# MCP_Teensy.net
KiCad netlist of a schematic drawn in EAGLE
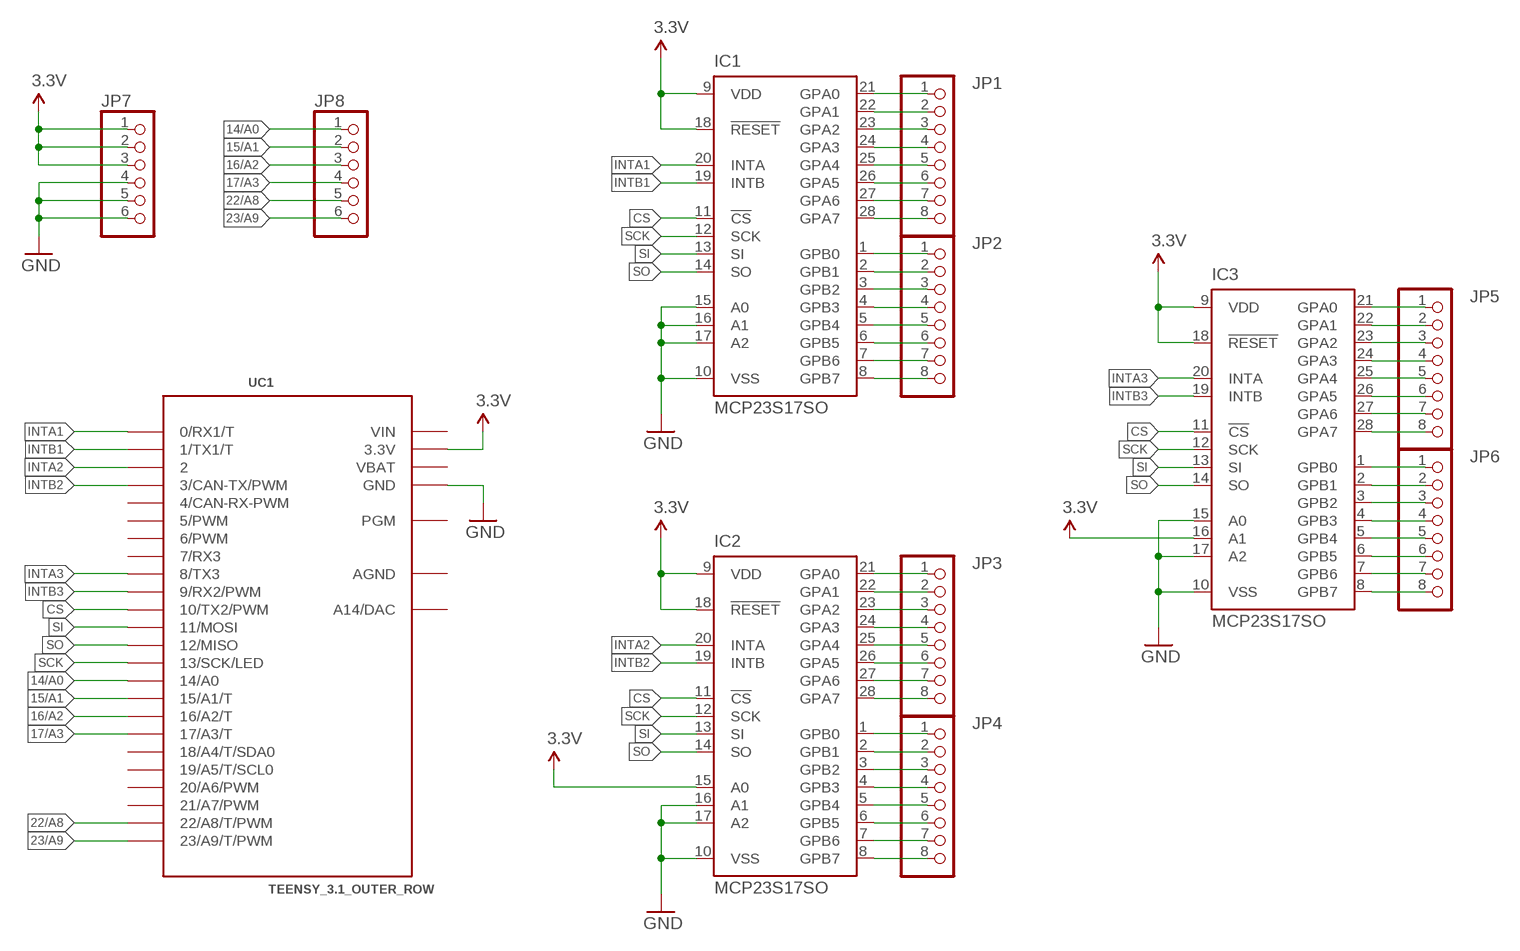
[diagram p0: schematic, sheet 1]

(export (version "E")
  (design (tool "Eeschema 10.0.6"))
  (components
    (comp (ref "IC1")
      (value "MCP23S17SO")
      (footprint "eagle-import:SO28W")
      (fields (field (name "MF") "MICROCHIP") (field (name "MPN") "MCP23S17-E/SO"))
      (libsource (lib "eagle-import") (part "MCP23S17SO"))
    )
    (comp (ref "IC2")
      (value "MCP23S17SO")
      (footprint "eagle-import:SO28W")
      (fields (field (name "MF") "MICROCHIP") (field (name "MPN") "MCP23S17-E/SO"))
      (libsource (lib "eagle-import") (part "MCP23S17SO"))
    )
    (comp (ref "IC3")
      (value "MCP23S17SO")
      (footprint "eagle-import:SO28W")
      (fields (field (name "MF") "MICROCHIP") (field (name "MPN") "MCP23S17-E/SO"))
      (libsource (lib "eagle-import") (part "MCP23S17SO"))
    )
    (comp (ref "JP1")
      (value "PINHD-1X8LOCK")
      (footprint "eagle-import:1X08-LOCK")
      (libsource (lib "eagle-import") (part "PINHD-1X8LOCK"))
    )
    (comp (ref "JP2")
      (value "PINHD-1X8LOCK")
      (footprint "eagle-import:1X08-LOCK")
      (libsource (lib "eagle-import") (part "PINHD-1X8LOCK"))
    )
    (comp (ref "JP3")
      (value "PINHD-1X8LOCK")
      (footprint "eagle-import:1X08-LOCK")
      (libsource (lib "eagle-import") (part "PINHD-1X8LOCK"))
    )
    (comp (ref "JP4")
      (value "PINHD-1X8LOCK")
      (footprint "eagle-import:1X08-LOCK")
      (libsource (lib "eagle-import") (part "PINHD-1X8LOCK"))
    )
    (comp (ref "JP5")
      (value "PINHD-1X8LOCK")
      (footprint "eagle-import:1X08-LOCK")
      (libsource (lib "eagle-import") (part "PINHD-1X8LOCK"))
    )
    (comp (ref "JP6")
      (value "PINHD-1X8LOCK")
      (footprint "eagle-import:1X08-LOCK")
      (libsource (lib "eagle-import") (part "PINHD-1X8LOCK"))
    )
    (comp (ref "JP7")
      (value "PINHD-1X6LOCK")
      (footprint "eagle-import:1X06-BIGLOCK")
      (libsource (lib "eagle-import") (part "PINHD-1X6LOCK"))
    )
    (comp (ref "JP8")
      (value "PINHD-1X6LOCK")
      (footprint "eagle-import:1X06-BIGLOCK")
      (libsource (lib "eagle-import") (part "PINHD-1X6LOCK"))
    )
    (comp (ref "UC1")
      (value "TEENSY_3.1_OUTER_ROW")
      (footprint "eagle-import:TEENSY3-OUTER_ROW")
      (libsource (lib "eagle-import") (part "TEENSY_3.1_OUTER_ROW"))
    )
  )
  (nets
    (net (code "1") (name "/AGND") (class "Default")
      (node (ref "UC1") (pin "AGND") (pinfunction "AGND_AGND") (pintype "power_in"))
    )
    (net (code "2") (name "/VBAT") (class "Default")
      (node (ref "UC1") (pin "VBAT") (pinfunction "VBAT_VBAT") (pintype "power_in"))
    )
    (net (code "3") (name "/VIN") (class "Default")
      (node (ref "UC1") (pin "VIN") (pinfunction "VIN_VIN") (pintype "power_in"))
    )
    (net (code "4") (name "3.3V") (class "Default")
      (node (ref "IC1") (pin "18") (pinfunction "~{RESET}_18") (pintype "input"))
      (node (ref "IC1") (pin "9") (pinfunction "VDD_9") (pintype "power_in"))
      (node (ref "IC2") (pin "15") (pinfunction "A0_15") (pintype "input"))
      (node (ref "IC2") (pin "18") (pinfunction "~{RESET}_18") (pintype "input"))
      (node (ref "IC2") (pin "9") (pinfunction "VDD_9") (pintype "power_in"))
      (node (ref "IC3") (pin "16") (pinfunction "A1_16") (pintype "input"))
      (node (ref "IC3") (pin "18") (pinfunction "~{RESET}_18") (pintype "input"))
      (node (ref "IC3") (pin "9") (pinfunction "VDD_9") (pintype "power_in"))
      (node (ref "JP7") (pin "1") (pinfunction "1_1") (pintype "passive"))
      (node (ref "JP7") (pin "2") (pinfunction "2_2") (pintype "passive"))
      (node (ref "JP7") (pin "3") (pinfunction "3_3") (pintype "passive"))
      (node (ref "UC1") (pin "3.3V") (pinfunction "3.3V_3.3V") (pintype "power_in"))
      (node (ref "UC1") (pin "3.3V1") (pinfunction "3.3V_3.3V1") (pintype "power_in"))
    )
    (net (code "5") (name "14{slash}A0") (class "Default")
      (node (ref "JP8") (pin "1") (pinfunction "1_1") (pintype "passive"))
      (node (ref "UC1") (pin "14/A0") (pinfunction "14/A0_14/A0") (pintype "bidirectional"))
    )
    (net (code "6") (name "15{slash}A1") (class "Default")
      (node (ref "JP8") (pin "2") (pinfunction "2_2") (pintype "passive"))
      (node (ref "UC1") (pin "15/A1") (pinfunction "15/A1/T_15/A1") (pintype "bidirectional"))
    )
    (net (code "7") (name "16{slash}A2") (class "Default")
      (node (ref "JP8") (pin "3") (pinfunction "3_3") (pintype "passive"))
      (node (ref "UC1") (pin "16/A2") (pinfunction "16/A2/T_16/A2") (pintype "bidirectional"))
    )
    (net (code "8") (name "17{slash}A3") (class "Default")
      (node (ref "JP8") (pin "4") (pinfunction "4_4") (pintype "passive"))
      (node (ref "UC1") (pin "17/A3") (pinfunction "17/A3/T_17/A3") (pintype "bidirectional"))
    )
    (net (code "9") (name "22{slash}A8") (class "Default")
      (node (ref "JP8") (pin "5") (pinfunction "5_5") (pintype "passive"))
      (node (ref "UC1") (pin "22/A8") (pinfunction "22/A8/T/PWM_22/A8") (pintype "bidirectional"))
    )
    (net (code "10") (name "23{slash}A9") (class "Default")
      (node (ref "JP8") (pin "6") (pinfunction "6_6") (pintype "passive"))
      (node (ref "UC1") (pin "23/A9") (pinfunction "23/A9/T/PWM_23/A9") (pintype "bidirectional"))
    )
    (net (code "11") (name "CS") (class "Default")
      (node (ref "IC1") (pin "11") (pinfunction "~{CS}_11") (pintype "input"))
      (node (ref "IC2") (pin "11") (pinfunction "~{CS}_11") (pintype "input"))
      (node (ref "IC3") (pin "11") (pinfunction "~{CS}_11") (pintype "input"))
      (node (ref "UC1") (pin "10") (pinfunction "10/TX2/PWM_10") (pintype "bidirectional"))
    )
    (net (code "12") (name "GND") (class "Default")
      (node (ref "IC1") (pin "10") (pinfunction "VSS_10") (pintype "power_in"))
      (node (ref "IC1") (pin "15") (pinfunction "A0_15") (pintype "input"))
      (node (ref "IC1") (pin "16") (pinfunction "A1_16") (pintype "input"))
      (node (ref "IC1") (pin "17") (pinfunction "A2_17") (pintype "input"))
      (node (ref "IC2") (pin "10") (pinfunction "VSS_10") (pintype "power_in"))
      (node (ref "IC2") (pin "16") (pinfunction "A1_16") (pintype "input"))
      (node (ref "IC2") (pin "17") (pinfunction "A2_17") (pintype "input"))
      (node (ref "IC3") (pin "10") (pinfunction "VSS_10") (pintype "power_in"))
      (node (ref "IC3") (pin "15") (pinfunction "A0_15") (pintype "input"))
      (node (ref "IC3") (pin "17") (pinfunction "A2_17") (pintype "input"))
      (node (ref "JP7") (pin "4") (pinfunction "4_4") (pintype "passive"))
      (node (ref "JP7") (pin "5") (pinfunction "5_5") (pintype "passive"))
      (node (ref "JP7") (pin "6") (pinfunction "6_6") (pintype "passive"))
      (node (ref "UC1") (pin "GND") (pinfunction "GND_GND") (pintype "power_in"))
      (node (ref "UC1") (pin "GND1") (pinfunction "GND_GND1") (pintype "power_in"))
    )
    (net (code "13") (name "INTA1") (class "Default")
      (node (ref "IC1") (pin "20") (pinfunction "INTA_20") (pintype "output"))
      (node (ref "UC1") (pin "0") (pinfunction "0/RX1/T_0") (pintype "bidirectional"))
    )
    (net (code "14") (name "INTA2") (class "Default")
      (node (ref "IC2") (pin "20") (pinfunction "INTA_20") (pintype "output"))
      (node (ref "UC1") (pin "2") (pinfunction "2_2") (pintype "bidirectional"))
    )
    (net (code "15") (name "INTA3") (class "Default")
      (node (ref "IC3") (pin "20") (pinfunction "INTA_20") (pintype "output"))
      (node (ref "UC1") (pin "8") (pinfunction "8/TX3_8") (pintype "bidirectional"))
    )
    (net (code "16") (name "INTB1") (class "Default")
      (node (ref "IC1") (pin "19") (pinfunction "INTB_19") (pintype "output"))
      (node (ref "UC1") (pin "1") (pinfunction "1/TX1/T_1") (pintype "bidirectional"))
    )
    (net (code "17") (name "INTB2") (class "Default")
      (node (ref "IC2") (pin "19") (pinfunction "INTB_19") (pintype "output"))
      (node (ref "UC1") (pin "3") (pinfunction "3/CAN-TX/PWM_3") (pintype "bidirectional"))
    )
    (net (code "18") (name "INTB3") (class "Default")
      (node (ref "IC3") (pin "19") (pinfunction "INTB_19") (pintype "output"))
      (node (ref "UC1") (pin "9") (pinfunction "9/RX2/PWM_9") (pintype "bidirectional"))
    )
    (net (code "19") (name "Net-(IC1-GPA0)") (class "Default")
      (node (ref "IC1") (pin "21") (pinfunction "GPA0_21") (pintype "bidirectional"))
      (node (ref "JP1") (pin "1") (pinfunction "1_1") (pintype "passive"))
    )
    (net (code "20") (name "Net-(IC1-GPA1)") (class "Default")
      (node (ref "IC1") (pin "22") (pinfunction "GPA1_22") (pintype "bidirectional"))
      (node (ref "JP1") (pin "2") (pinfunction "2_2") (pintype "passive"))
    )
    (net (code "21") (name "Net-(IC1-GPA2)") (class "Default")
      (node (ref "IC1") (pin "23") (pinfunction "GPA2_23") (pintype "bidirectional"))
      (node (ref "JP1") (pin "3") (pinfunction "3_3") (pintype "passive"))
    )
    (net (code "22") (name "Net-(IC1-GPA3)") (class "Default")
      (node (ref "IC1") (pin "24") (pinfunction "GPA3_24") (pintype "bidirectional"))
      (node (ref "JP1") (pin "4") (pinfunction "4_4") (pintype "passive"))
    )
    (net (code "23") (name "Net-(IC1-GPA4)") (class "Default")
      (node (ref "IC1") (pin "25") (pinfunction "GPA4_25") (pintype "bidirectional"))
      (node (ref "JP1") (pin "5") (pinfunction "5_5") (pintype "passive"))
    )
    (net (code "24") (name "Net-(IC1-GPA5)") (class "Default")
      (node (ref "IC1") (pin "26") (pinfunction "GPA5_26") (pintype "bidirectional"))
      (node (ref "JP1") (pin "6") (pinfunction "6_6") (pintype "passive"))
    )
    (net (code "25") (name "Net-(IC1-GPA6)") (class "Default")
      (node (ref "IC1") (pin "27") (pinfunction "GPA6_27") (pintype "bidirectional"))
      (node (ref "JP1") (pin "7") (pinfunction "7_7") (pintype "passive"))
    )
    (net (code "26") (name "Net-(IC1-GPA7)") (class "Default")
      (node (ref "IC1") (pin "28") (pinfunction "GPA7_28") (pintype "bidirectional"))
      (node (ref "JP1") (pin "8") (pinfunction "8_8") (pintype "passive"))
    )
    (net (code "27") (name "Net-(IC1-GPB0)") (class "Default")
      (node (ref "IC1") (pin "1") (pinfunction "GPB0_1") (pintype "bidirectional"))
      (node (ref "JP2") (pin "1") (pinfunction "1_1") (pintype "passive"))
    )
    (net (code "28") (name "Net-(IC1-GPB1)") (class "Default")
      (node (ref "IC1") (pin "2") (pinfunction "GPB1_2") (pintype "bidirectional"))
      (node (ref "JP2") (pin "2") (pinfunction "2_2") (pintype "passive"))
    )
    (net (code "29") (name "Net-(IC1-GPB2)") (class "Default")
      (node (ref "IC1") (pin "3") (pinfunction "GPB2_3") (pintype "bidirectional"))
      (node (ref "JP2") (pin "3") (pinfunction "3_3") (pintype "passive"))
    )
    (net (code "30") (name "Net-(IC1-GPB3)") (class "Default")
      (node (ref "IC1") (pin "4") (pinfunction "GPB3_4") (pintype "bidirectional"))
      (node (ref "JP2") (pin "4") (pinfunction "4_4") (pintype "passive"))
    )
    (net (code "31") (name "Net-(IC1-GPB4)") (class "Default")
      (node (ref "IC1") (pin "5") (pinfunction "GPB4_5") (pintype "bidirectional"))
      (node (ref "JP2") (pin "5") (pinfunction "5_5") (pintype "passive"))
    )
    (net (code "32") (name "Net-(IC1-GPB5)") (class "Default")
      (node (ref "IC1") (pin "6") (pinfunction "GPB5_6") (pintype "bidirectional"))
      (node (ref "JP2") (pin "6") (pinfunction "6_6") (pintype "passive"))
    )
    (net (code "33") (name "Net-(IC1-GPB6)") (class "Default")
      (node (ref "IC1") (pin "7") (pinfunction "GPB6_7") (pintype "bidirectional"))
      (node (ref "JP2") (pin "7") (pinfunction "7_7") (pintype "passive"))
    )
    (net (code "34") (name "Net-(IC1-GPB7)") (class "Default")
      (node (ref "IC1") (pin "8") (pinfunction "GPB7_8") (pintype "bidirectional"))
      (node (ref "JP2") (pin "8") (pinfunction "8_8") (pintype "passive"))
    )
    (net (code "35") (name "Net-(IC2-GPA0)") (class "Default")
      (node (ref "IC2") (pin "21") (pinfunction "GPA0_21") (pintype "bidirectional"))
      (node (ref "JP3") (pin "1") (pinfunction "1_1") (pintype "passive"))
    )
    (net (code "36") (name "Net-(IC2-GPA1)") (class "Default")
      (node (ref "IC2") (pin "22") (pinfunction "GPA1_22") (pintype "bidirectional"))
      (node (ref "JP3") (pin "2") (pinfunction "2_2") (pintype "passive"))
    )
    (net (code "37") (name "Net-(IC2-GPA2)") (class "Default")
      (node (ref "IC2") (pin "23") (pinfunction "GPA2_23") (pintype "bidirectional"))
      (node (ref "JP3") (pin "3") (pinfunction "3_3") (pintype "passive"))
    )
    (net (code "38") (name "Net-(IC2-GPA3)") (class "Default")
      (node (ref "IC2") (pin "24") (pinfunction "GPA3_24") (pintype "bidirectional"))
      (node (ref "JP3") (pin "4") (pinfunction "4_4") (pintype "passive"))
    )
    (net (code "39") (name "Net-(IC2-GPA4)") (class "Default")
      (node (ref "IC2") (pin "25") (pinfunction "GPA4_25") (pintype "bidirectional"))
      (node (ref "JP3") (pin "5") (pinfunction "5_5") (pintype "passive"))
    )
    (net (code "40") (name "Net-(IC2-GPA5)") (class "Default")
      (node (ref "IC2") (pin "26") (pinfunction "GPA5_26") (pintype "bidirectional"))
      (node (ref "JP3") (pin "6") (pinfunction "6_6") (pintype "passive"))
    )
    (net (code "41") (name "Net-(IC2-GPA6)") (class "Default")
      (node (ref "IC2") (pin "27") (pinfunction "GPA6_27") (pintype "bidirectional"))
      (node (ref "JP3") (pin "7") (pinfunction "7_7") (pintype "passive"))
    )
    (net (code "42") (name "Net-(IC2-GPA7)") (class "Default")
      (node (ref "IC2") (pin "28") (pinfunction "GPA7_28") (pintype "bidirectional"))
      (node (ref "JP3") (pin "8") (pinfunction "8_8") (pintype "passive"))
    )
    (net (code "43") (name "Net-(IC2-GPB0)") (class "Default")
      (node (ref "IC2") (pin "1") (pinfunction "GPB0_1") (pintype "bidirectional"))
      (node (ref "JP4") (pin "1") (pinfunction "1_1") (pintype "passive"))
    )
    (net (code "44") (name "Net-(IC2-GPB1)") (class "Default")
      (node (ref "IC2") (pin "2") (pinfunction "GPB1_2") (pintype "bidirectional"))
      (node (ref "JP4") (pin "2") (pinfunction "2_2") (pintype "passive"))
    )
    (net (code "45") (name "Net-(IC2-GPB2)") (class "Default")
      (node (ref "IC2") (pin "3") (pinfunction "GPB2_3") (pintype "bidirectional"))
      (node (ref "JP4") (pin "3") (pinfunction "3_3") (pintype "passive"))
    )
    (net (code "46") (name "Net-(IC2-GPB3)") (class "Default")
      (node (ref "IC2") (pin "4") (pinfunction "GPB3_4") (pintype "bidirectional"))
      (node (ref "JP4") (pin "4") (pinfunction "4_4") (pintype "passive"))
    )
    (net (code "47") (name "Net-(IC2-GPB4)") (class "Default")
      (node (ref "IC2") (pin "5") (pinfunction "GPB4_5") (pintype "bidirectional"))
      (node (ref "JP4") (pin "5") (pinfunction "5_5") (pintype "passive"))
    )
    (net (code "48") (name "Net-(IC2-GPB5)") (class "Default")
      (node (ref "IC2") (pin "6") (pinfunction "GPB5_6") (pintype "bidirectional"))
      (node (ref "JP4") (pin "6") (pinfunction "6_6") (pintype "passive"))
    )
    (net (code "49") (name "Net-(IC2-GPB6)") (class "Default")
      (node (ref "IC2") (pin "7") (pinfunction "GPB6_7") (pintype "bidirectional"))
      (node (ref "JP4") (pin "7") (pinfunction "7_7") (pintype "passive"))
    )
    (net (code "50") (name "Net-(IC2-GPB7)") (class "Default")
      (node (ref "IC2") (pin "8") (pinfunction "GPB7_8") (pintype "bidirectional"))
      (node (ref "JP4") (pin "8") (pinfunction "8_8") (pintype "passive"))
    )
    (net (code "51") (name "Net-(IC3-GPA0)") (class "Default")
      (node (ref "IC3") (pin "21") (pinfunction "GPA0_21") (pintype "bidirectional"))
      (node (ref "JP5") (pin "1") (pinfunction "1_1") (pintype "passive"))
    )
    (net (code "52") (name "Net-(IC3-GPA1)") (class "Default")
      (node (ref "IC3") (pin "22") (pinfunction "GPA1_22") (pintype "bidirectional"))
      (node (ref "JP5") (pin "2") (pinfunction "2_2") (pintype "passive"))
    )
    (net (code "53") (name "Net-(IC3-GPA2)") (class "Default")
      (node (ref "IC3") (pin "23") (pinfunction "GPA2_23") (pintype "bidirectional"))
      (node (ref "JP5") (pin "3") (pinfunction "3_3") (pintype "passive"))
    )
    (net (code "54") (name "Net-(IC3-GPA3)") (class "Default")
      (node (ref "IC3") (pin "24") (pinfunction "GPA3_24") (pintype "bidirectional"))
      (node (ref "JP5") (pin "4") (pinfunction "4_4") (pintype "passive"))
    )
    (net (code "55") (name "Net-(IC3-GPA4)") (class "Default")
      (node (ref "IC3") (pin "25") (pinfunction "GPA4_25") (pintype "bidirectional"))
      (node (ref "JP5") (pin "5") (pinfunction "5_5") (pintype "passive"))
    )
    (net (code "56") (name "Net-(IC3-GPA5)") (class "Default")
      (node (ref "IC3") (pin "26") (pinfunction "GPA5_26") (pintype "bidirectional"))
      (node (ref "JP5") (pin "6") (pinfunction "6_6") (pintype "passive"))
    )
    (net (code "57") (name "Net-(IC3-GPA6)") (class "Default")
      (node (ref "IC3") (pin "27") (pinfunction "GPA6_27") (pintype "bidirectional"))
      (node (ref "JP5") (pin "7") (pinfunction "7_7") (pintype "passive"))
    )
    (net (code "58") (name "Net-(IC3-GPA7)") (class "Default")
      (node (ref "IC3") (pin "28") (pinfunction "GPA7_28") (pintype "bidirectional"))
      (node (ref "JP5") (pin "8") (pinfunction "8_8") (pintype "passive"))
    )
    (net (code "59") (name "Net-(IC3-GPB0)") (class "Default")
      (node (ref "IC3") (pin "1") (pinfunction "GPB0_1") (pintype "bidirectional"))
      (node (ref "JP6") (pin "1") (pinfunction "1_1") (pintype "passive"))
    )
    (net (code "60") (name "Net-(IC3-GPB1)") (class "Default")
      (node (ref "IC3") (pin "2") (pinfunction "GPB1_2") (pintype "bidirectional"))
      (node (ref "JP6") (pin "2") (pinfunction "2_2") (pintype "passive"))
    )
    (net (code "61") (name "Net-(IC3-GPB2)") (class "Default")
      (node (ref "IC3") (pin "3") (pinfunction "GPB2_3") (pintype "bidirectional"))
      (node (ref "JP6") (pin "3") (pinfunction "3_3") (pintype "passive"))
    )
    (net (code "62") (name "Net-(IC3-GPB3)") (class "Default")
      (node (ref "IC3") (pin "4") (pinfunction "GPB3_4") (pintype "bidirectional"))
      (node (ref "JP6") (pin "4") (pinfunction "4_4") (pintype "passive"))
    )
    (net (code "63") (name "Net-(IC3-GPB4)") (class "Default")
      (node (ref "IC3") (pin "5") (pinfunction "GPB4_5") (pintype "bidirectional"))
      (node (ref "JP6") (pin "5") (pinfunction "5_5") (pintype "passive"))
    )
    (net (code "64") (name "Net-(IC3-GPB5)") (class "Default")
      (node (ref "IC3") (pin "6") (pinfunction "GPB5_6") (pintype "bidirectional"))
      (node (ref "JP6") (pin "6") (pinfunction "6_6") (pintype "passive"))
    )
    (net (code "65") (name "Net-(IC3-GPB6)") (class "Default")
      (node (ref "IC3") (pin "7") (pinfunction "GPB6_7") (pintype "bidirectional"))
      (node (ref "JP6") (pin "7") (pinfunction "7_7") (pintype "passive"))
    )
    (net (code "66") (name "Net-(IC3-GPB7)") (class "Default")
      (node (ref "IC3") (pin "8") (pinfunction "GPB7_8") (pintype "bidirectional"))
      (node (ref "JP6") (pin "8") (pinfunction "8_8") (pintype "passive"))
    )
    (net (code "67") (name "SCK") (class "Default")
      (node (ref "IC1") (pin "12") (pinfunction "SCK_12") (pintype "input"))
      (node (ref "IC2") (pin "12") (pinfunction "SCK_12") (pintype "input"))
      (node (ref "IC3") (pin "12") (pinfunction "SCK_12") (pintype "input"))
      (node (ref "UC1") (pin "13") (pinfunction "13/SCK/LED_13") (pintype "bidirectional"))
    )
    (net (code "68") (name "SI") (class "Default")
      (node (ref "IC1") (pin "13") (pinfunction "SI_13") (pintype "input"))
      (node (ref "IC2") (pin "13") (pinfunction "SI_13") (pintype "input"))
      (node (ref "IC3") (pin "13") (pinfunction "SI_13") (pintype "input"))
      (node (ref "UC1") (pin "11") (pinfunction "11/MOSI_11") (pintype "bidirectional"))
    )
    (net (code "69") (name "SO") (class "Default")
      (node (ref "IC1") (pin "14") (pinfunction "SO_14") (pintype "output"))
      (node (ref "IC2") (pin "14") (pinfunction "SO_14") (pintype "output"))
      (node (ref "IC3") (pin "14") (pinfunction "SO_14") (pintype "output"))
      (node (ref "UC1") (pin "12") (pinfunction "12/MISO_12") (pintype "bidirectional"))
    )
    (net (code "70") (name "unconnected-(UC1-4{slash}CAN-RX-PWM-Pad4)") (class "Default")
      (node (ref "UC1") (pin "4") (pinfunction "4/CAN-RX-PWM_4") (pintype "bidirectional"))
    )
    (net (code "71") (name "unconnected-(UC1-5{slash}PWM-Pad5)") (class "Default")
      (node (ref "UC1") (pin "5") (pinfunction "5/PWM_5") (pintype "bidirectional"))
    )
    (net (code "72") (name "unconnected-(UC1-6{slash}PWM-Pad6)") (class "Default")
      (node (ref "UC1") (pin "6") (pinfunction "6/PWM_6") (pintype "bidirectional"))
    )
    (net (code "73") (name "unconnected-(UC1-7{slash}RX3-Pad7)") (class "Default")
      (node (ref "UC1") (pin "7") (pinfunction "7/RX3_7") (pintype "bidirectional"))
    )
    (net (code "74") (name "unconnected-(UC1-18{slash}A4{slash}T{slash}SDA0-Pad18{slash}A4)") (class "Default")
      (node (ref "UC1") (pin "18/A4") (pinfunction "18/A4/T/SDA0_18/A4") (pintype "bidirectional"))
    )
    (net (code "75") (name "unconnected-(UC1-19{slash}A5{slash}T{slash}SCL0-Pad19{slash}A5)") (class "Default")
      (node (ref "UC1") (pin "19/A5") (pinfunction "19/A5/T/SCL0_19/A5") (pintype "bidirectional"))
    )
    (net (code "76") (name "unconnected-(UC1-20{slash}A6{slash}PWM-Pad20{slash}A6)") (class "Default")
      (node (ref "UC1") (pin "20/A6") (pinfunction "20/A6/PWM_20/A6") (pintype "bidirectional"))
    )
    (net (code "77") (name "unconnected-(UC1-21{slash}A7{slash}PWM-Pad21{slash}A7)") (class "Default")
      (node (ref "UC1") (pin "21/A7") (pinfunction "21/A7/PWM_21/A7") (pintype "bidirectional"))
    )
    (net (code "78") (name "unconnected-(UC1-A14{slash}DAC-PadRESET{slash}DAC)") (class "Default")
      (node (ref "UC1") (pin "RESET/DAC") (pinfunction "A14/DAC_RESET/DAC") (pintype "bidirectional"))
    )
    (net (code "79") (name "unconnected-(UC1-PadPGM)") (class "Default")
      (node (ref "UC1") (pin "PGM") (pinfunction "PGM_PGM") (pintype "bidirectional"))
    )
  )
)
